# RH031_1.net
KiCad netlist of a schematic drawn in EAGLE
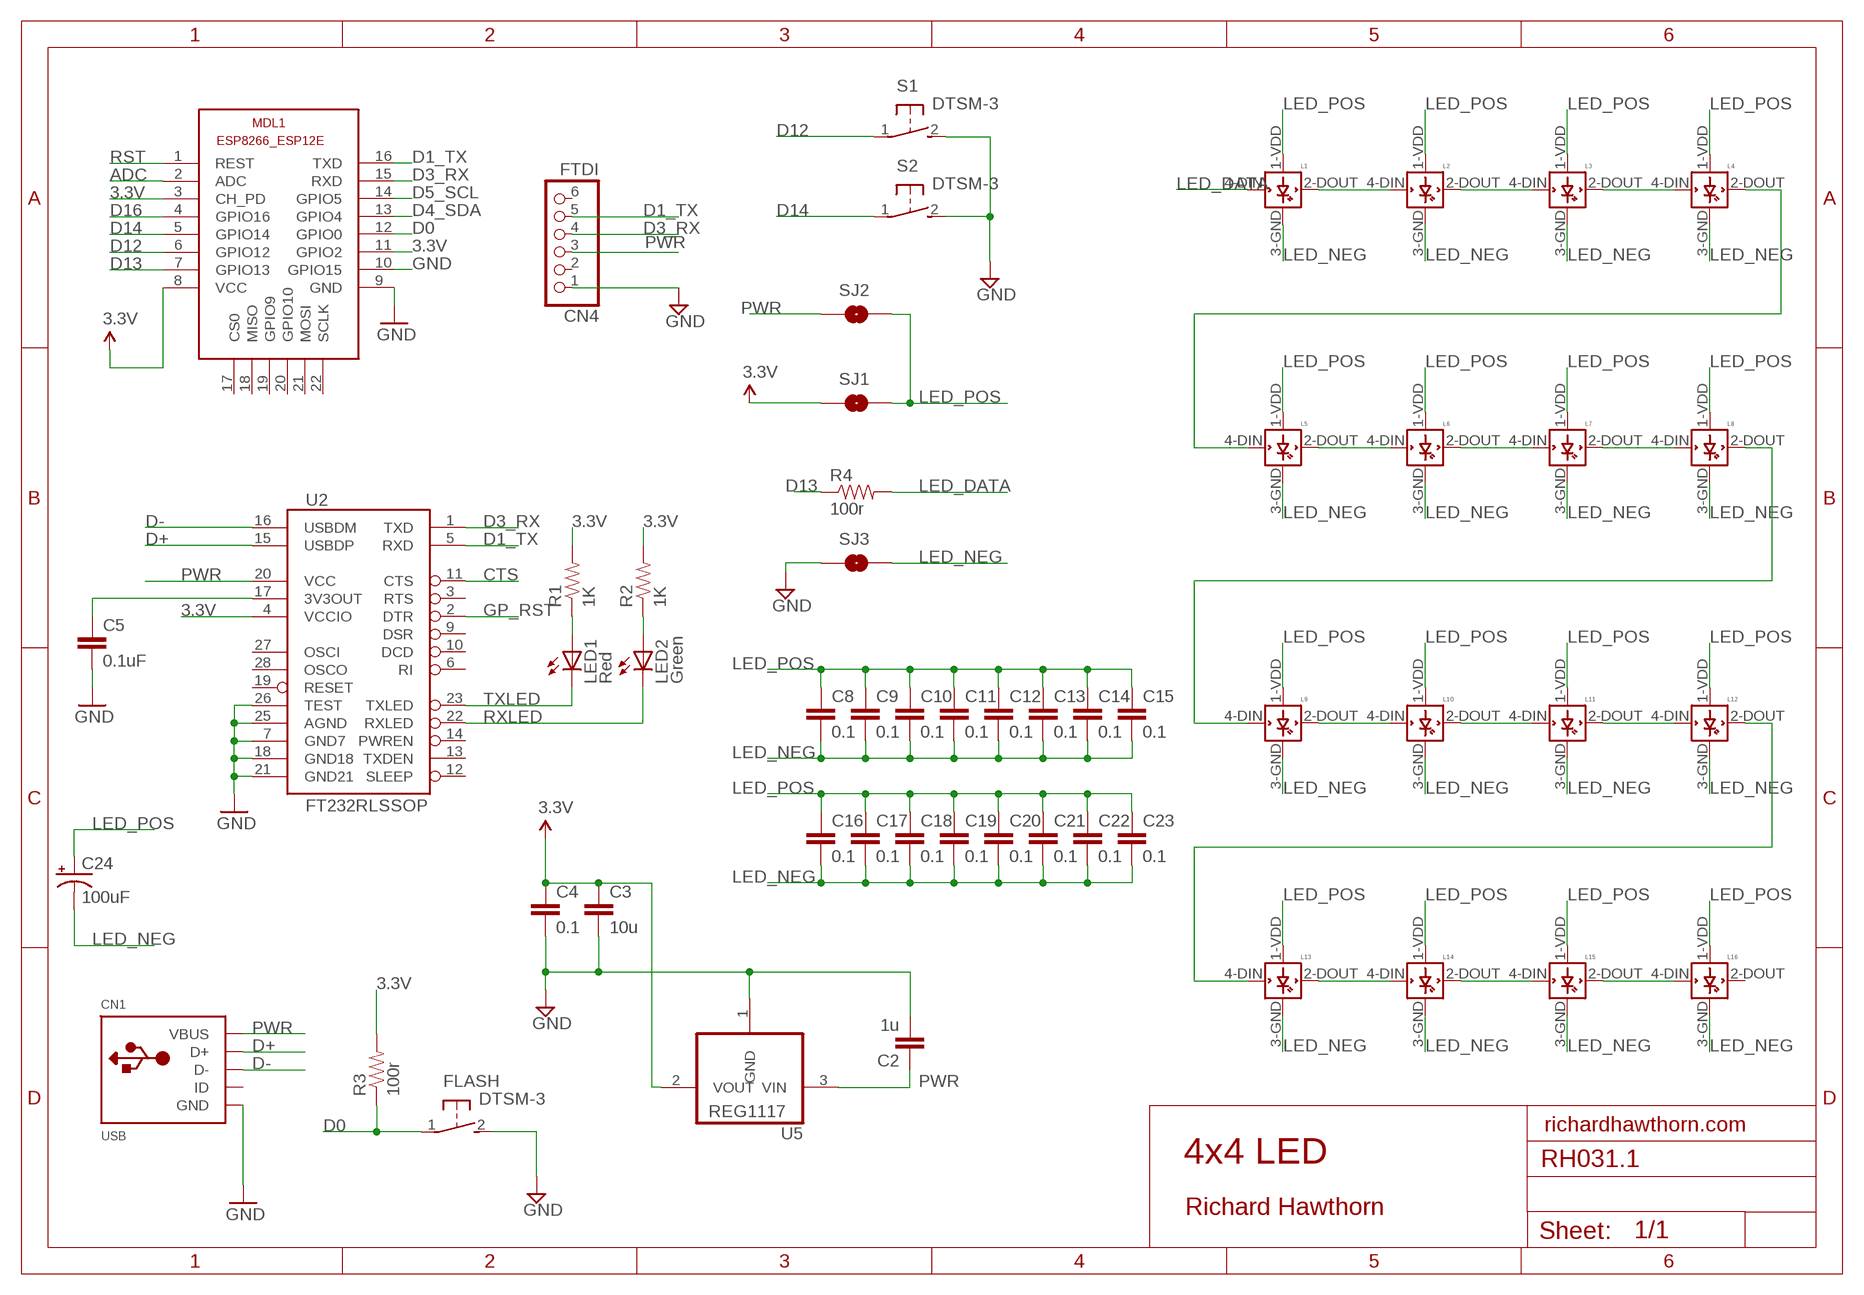
[diagram p0: schematic, sheet 1]

(export (version "E")
  (design (tool "Eeschema 10.0.6"))
  (components
    (comp (ref "C2")
      (value "1u")
      (footprint "eagle-import:0603-CAP")
      (libsource (lib "eagle-import") (part "CAP0603-CAP"))
    )
    (comp (ref "C3")
      (value "10u")
      (footprint "eagle-import:0805-CAP")
      (libsource (lib "eagle-import") (part "CAP0805-CAP"))
    )
    (comp (ref "C4")
      (value "0.1")
      (footprint "eagle-import:0603-CAP")
      (libsource (lib "eagle-import") (part "CAP0603-CAP"))
    )
    (comp (ref "C5")
      (value "0.1uF")
      (footprint "eagle-import:0805")
      (libsource (lib "eagle-import") (part "SparkFun_CAP0805"))
    )
    (comp (ref "C8")
      (value "0.1")
      (footprint "eagle-import:0603-CAP")
      (libsource (lib "eagle-import") (part "CAP0603-CAP"))
    )
    (comp (ref "C9")
      (value "0.1")
      (footprint "eagle-import:0603-CAP")
      (libsource (lib "eagle-import") (part "CAP0603-CAP"))
    )
    (comp (ref "C10")
      (value "0.1")
      (footprint "eagle-import:0603-CAP")
      (libsource (lib "eagle-import") (part "CAP0603-CAP"))
    )
    (comp (ref "C11")
      (value "0.1")
      (footprint "eagle-import:0603-CAP")
      (libsource (lib "eagle-import") (part "CAP0603-CAP"))
    )
    (comp (ref "C12")
      (value "0.1")
      (footprint "eagle-import:0603-CAP")
      (libsource (lib "eagle-import") (part "CAP0603-CAP"))
    )
    (comp (ref "C13")
      (value "0.1")
      (footprint "eagle-import:0603-CAP")
      (libsource (lib "eagle-import") (part "CAP0603-CAP"))
    )
    (comp (ref "C14")
      (value "0.1")
      (footprint "eagle-import:0603-CAP")
      (libsource (lib "eagle-import") (part "CAP0603-CAP"))
    )
    (comp (ref "C15")
      (value "0.1")
      (footprint "eagle-import:0603-CAP")
      (libsource (lib "eagle-import") (part "CAP0603-CAP"))
    )
    (comp (ref "C16")
      (value "0.1")
      (footprint "eagle-import:0603-CAP")
      (libsource (lib "eagle-import") (part "CAP0603-CAP"))
    )
    (comp (ref "C17")
      (value "0.1")
      (footprint "eagle-import:0603-CAP")
      (libsource (lib "eagle-import") (part "CAP0603-CAP"))
    )
    (comp (ref "C18")
      (value "0.1")
      (footprint "eagle-import:0603-CAP")
      (libsource (lib "eagle-import") (part "CAP0603-CAP"))
    )
    (comp (ref "C19")
      (value "0.1")
      (footprint "eagle-import:0603-CAP")
      (libsource (lib "eagle-import") (part "CAP0603-CAP"))
    )
    (comp (ref "C20")
      (value "0.1")
      (footprint "eagle-import:0603-CAP")
      (libsource (lib "eagle-import") (part "CAP0603-CAP"))
    )
    (comp (ref "C21")
      (value "0.1")
      (footprint "eagle-import:0603-CAP")
      (libsource (lib "eagle-import") (part "CAP0603-CAP"))
    )
    (comp (ref "C22")
      (value "0.1")
      (footprint "eagle-import:0603-CAP")
      (libsource (lib "eagle-import") (part "CAP0603-CAP"))
    )
    (comp (ref "C23")
      (value "0.1")
      (footprint "eagle-import:0603-CAP")
      (libsource (lib "eagle-import") (part "CAP0603-CAP"))
    )
    (comp (ref "C24")
      (value "100uF")
      (footprint "eagle-import:EIA7343")
      (libsource (lib "eagle-import") (part "100UF-10V-10%(TANT)"))
    )
    (comp (ref "CN1")
      (value "USB")
      (footprint "eagle-import:USB-MINIB")
      (libsource (lib "eagle-import") (part "USBMINIB"))
    )
    (comp (ref "CN4")
      (value "FTDI")
      (footprint "eagle-import:1X06")
      (libsource (lib "eagle-import") (part "PINHD-1X6"))
    )
    (comp (ref "FLASH")
      (value "DTSM-3")
      (footprint "eagle-import:DTSM-3")
      (libsource (lib "eagle-import") (part "DTSM-3"))
    )
    (comp (ref "L1")
      (value "WS2812B")
      (footprint "eagle-import:WS2812B")
      (libsource (lib "eagle-import") (part "WS2812B"))
    )
    (comp (ref "L2")
      (value "WS2812B")
      (footprint "eagle-import:WS2812B")
      (libsource (lib "eagle-import") (part "WS2812B"))
    )
    (comp (ref "L3")
      (value "WS2812B")
      (footprint "eagle-import:WS2812B")
      (libsource (lib "eagle-import") (part "WS2812B"))
    )
    (comp (ref "L4")
      (value "WS2812B")
      (footprint "eagle-import:WS2812B")
      (libsource (lib "eagle-import") (part "WS2812B"))
    )
    (comp (ref "L5")
      (value "WS2812B")
      (footprint "eagle-import:WS2812B")
      (libsource (lib "eagle-import") (part "WS2812B"))
    )
    (comp (ref "L6")
      (value "WS2812B")
      (footprint "eagle-import:WS2812B")
      (libsource (lib "eagle-import") (part "WS2812B"))
    )
    (comp (ref "L7")
      (value "WS2812B")
      (footprint "eagle-import:WS2812B")
      (libsource (lib "eagle-import") (part "WS2812B"))
    )
    (comp (ref "L8")
      (value "WS2812B")
      (footprint "eagle-import:WS2812B")
      (libsource (lib "eagle-import") (part "WS2812B"))
    )
    (comp (ref "L9")
      (value "WS2812B")
      (footprint "eagle-import:WS2812B")
      (libsource (lib "eagle-import") (part "WS2812B"))
    )
    (comp (ref "L10")
      (value "WS2812B")
      (footprint "eagle-import:WS2812B")
      (libsource (lib "eagle-import") (part "WS2812B"))
    )
    (comp (ref "L11")
      (value "WS2812B")
      (footprint "eagle-import:WS2812B")
      (libsource (lib "eagle-import") (part "WS2812B"))
    )
    (comp (ref "L12")
      (value "WS2812B")
      (footprint "eagle-import:WS2812B")
      (libsource (lib "eagle-import") (part "WS2812B"))
    )
    (comp (ref "L13")
      (value "WS2812B")
      (footprint "eagle-import:WS2812B")
      (libsource (lib "eagle-import") (part "WS2812B"))
    )
    (comp (ref "L14")
      (value "WS2812B")
      (footprint "eagle-import:WS2812B")
      (libsource (lib "eagle-import") (part "WS2812B"))
    )
    (comp (ref "L15")
      (value "WS2812B")
      (footprint "eagle-import:WS2812B")
      (libsource (lib "eagle-import") (part "WS2812B"))
    )
    (comp (ref "L16")
      (value "WS2812B")
      (footprint "eagle-import:WS2812B")
      (libsource (lib "eagle-import") (part "WS2812B"))
    )
    (comp (ref "LED1")
      (value "Red")
      (footprint "eagle-import:CHIPLED_0805")
      (libsource (lib "eagle-import") (part "LEDCHIPLED_0805"))
    )
    (comp (ref "LED2")
      (value "Green")
      (footprint "eagle-import:CHIPLED_0805")
      (libsource (lib "eagle-import") (part "LEDCHIPLED_0805"))
    )
    (comp (ref "MDL1")
      (value "ESP8266-12EESP8266-ESP12E")
      (footprint "eagle-import:ESP8266-ESP12E")
      (libsource (lib "eagle-import") (part "ESP8266-12EESP8266-ESP12E"))
    )
    (comp (ref "R1")
      (value "1K")
      (footprint "eagle-import:0805")
      (libsource (lib "eagle-import") (part "SparkFun_RESISTOR0805-RES"))
    )
    (comp (ref "R2")
      (value "1K")
      (footprint "eagle-import:0805")
      (libsource (lib "eagle-import") (part "SparkFun_RESISTOR0805-RES"))
    )
    (comp (ref "R3")
      (value "100r")
      (footprint "eagle-import:0603-RES")
      (libsource (lib "eagle-import") (part "RESISTOR0603-RES"))
    )
    (comp (ref "R4")
      (value "100r")
      (footprint "eagle-import:0603-RES")
      (libsource (lib "eagle-import") (part "RESISTOR0603-RES"))
    )
    (comp (ref "S1")
      (value "DTSM-3")
      (footprint "eagle-import:DTSM-3")
      (libsource (lib "eagle-import") (part "DTSM-3"))
    )
    (comp (ref "S2")
      (value "DTSM-3")
      (footprint "eagle-import:DTSM-3")
      (libsource (lib "eagle-import") (part "DTSM-3"))
    )
    (comp (ref "SJ1")
      (value "SOLDERJUMPERNO")
      (footprint "eagle-import:SJ_2S-NO")
      (libsource (lib "eagle-import") (part "SOLDERJUMPERNO"))
    )
    (comp (ref "SJ2")
      (value "SOLDERJUMPERNO")
      (footprint "eagle-import:SJ_2S-NO")
      (libsource (lib "eagle-import") (part "SOLDERJUMPERNO"))
    )
    (comp (ref "SJ3")
      (value "SOLDERJUMPERNO")
      (footprint "eagle-import:SJ_2S-NO")
      (libsource (lib "eagle-import") (part "SOLDERJUMPERNO"))
    )
    (comp (ref "U2")
      (value "FT232RLSSOP")
      (footprint "eagle-import:SSOP28DB")
      (libsource (lib "eagle-import") (part "FT232RLSSOP"))
    )
    (comp (ref "U5")
      (value "REG1117")
      (footprint "eagle-import:SOT223")
      (libsource (lib "eagle-import") (part "REG1117"))
    )
  )
  (nets
    (net (code "1") (name "/ADC") (class "Default")
      (node (ref "MDL1") (pin "2") (pinfunction "ADC_2") (pintype "bidirectional"))
    )
    (net (code "2") (name "/CTS") (class "Default")
      (node (ref "U2") (pin "11") (pinfunction "CTS_11") (pintype "input"))
    )
    (net (code "3") (name "/D+") (class "Default")
      (node (ref "CN1") (pin "D+") (pinfunction "D+_D+") (pintype "bidirectional"))
      (node (ref "U2") (pin "15") (pinfunction "USBDP_15") (pintype "bidirectional"))
    )
    (net (code "4") (name "/D-") (class "Default")
      (node (ref "CN1") (pin "D-") (pinfunction "D-_D-") (pintype "bidirectional"))
      (node (ref "U2") (pin "16") (pinfunction "USBDM_16") (pintype "bidirectional"))
    )
    (net (code "5") (name "/D0") (class "Default")
      (node (ref "FLASH") (pin "1") (pinfunction "1_1") (pintype "passive"))
      (node (ref "MDL1") (pin "12") (pinfunction "GPIO0_12") (pintype "bidirectional"))
      (node (ref "R3") (pin "1") (pinfunction "1_1") (pintype "passive"))
    )
    (net (code "6") (name "/D1_TX") (class "Default")
      (node (ref "CN4") (pin "5") (pinfunction "5_5") (pintype "passive"))
      (node (ref "MDL1") (pin "16") (pinfunction "TXD_16") (pintype "bidirectional"))
      (node (ref "U2") (pin "5") (pinfunction "RXD_5") (pintype "input"))
    )
    (net (code "7") (name "/D3_RX") (class "Default")
      (node (ref "CN4") (pin "4") (pinfunction "4_4") (pintype "passive"))
      (node (ref "MDL1") (pin "15") (pinfunction "RXD_15") (pintype "bidirectional"))
      (node (ref "U2") (pin "1") (pinfunction "TXD_1") (pintype "output"))
    )
    (net (code "8") (name "/D4_SDA") (class "Default")
      (node (ref "MDL1") (pin "13") (pinfunction "GPIO4_13") (pintype "bidirectional"))
    )
    (net (code "9") (name "/D5_SCL") (class "Default")
      (node (ref "MDL1") (pin "14") (pinfunction "GPIO5_14") (pintype "bidirectional"))
    )
    (net (code "10") (name "/D12") (class "Default")
      (node (ref "MDL1") (pin "6") (pinfunction "GPIO12_6") (pintype "bidirectional"))
      (node (ref "S1") (pin "1") (pinfunction "1_1") (pintype "passive"))
    )
    (net (code "11") (name "/D13") (class "Default")
      (node (ref "MDL1") (pin "7") (pinfunction "GPIO13_7") (pintype "bidirectional"))
      (node (ref "R4") (pin "1") (pinfunction "1_1") (pintype "passive"))
    )
    (net (code "12") (name "/D14") (class "Default")
      (node (ref "MDL1") (pin "5") (pinfunction "GPIO14_5") (pintype "bidirectional"))
      (node (ref "S2") (pin "1") (pinfunction "1_1") (pintype "passive"))
    )
    (net (code "13") (name "/D16") (class "Default")
      (node (ref "MDL1") (pin "4") (pinfunction "GPIO16_4") (pintype "bidirectional"))
    )
    (net (code "14") (name "/GP_RST") (class "Default")
      (node (ref "U2") (pin "2") (pinfunction "DTR_2") (pintype "output"))
    )
    (net (code "15") (name "/LED_DATA") (class "Default")
      (node (ref "L1") (pin "4-DIN") (pinfunction "DIN_4-DIN") (pintype "input"))
      (node (ref "R4") (pin "2") (pinfunction "2_2") (pintype "passive"))
    )
    (net (code "16") (name "/LED_NEG") (class "Default")
      (node (ref "C10") (pin "2") (pinfunction "2_2") (pintype "passive"))
      (node (ref "C11") (pin "2") (pinfunction "2_2") (pintype "passive"))
      (node (ref "C12") (pin "2") (pinfunction "2_2") (pintype "passive"))
      (node (ref "C13") (pin "2") (pinfunction "2_2") (pintype "passive"))
      (node (ref "C14") (pin "2") (pinfunction "2_2") (pintype "passive"))
      (node (ref "C15") (pin "2") (pinfunction "2_2") (pintype "passive"))
      (node (ref "C16") (pin "2") (pinfunction "2_2") (pintype "passive"))
      (node (ref "C17") (pin "2") (pinfunction "2_2") (pintype "passive"))
      (node (ref "C18") (pin "2") (pinfunction "2_2") (pintype "passive"))
      (node (ref "C19") (pin "2") (pinfunction "2_2") (pintype "passive"))
      (node (ref "C20") (pin "2") (pinfunction "2_2") (pintype "passive"))
      (node (ref "C21") (pin "2") (pinfunction "2_2") (pintype "passive"))
      (node (ref "C22") (pin "2") (pinfunction "2_2") (pintype "passive"))
      (node (ref "C23") (pin "2") (pinfunction "2_2") (pintype "passive"))
      (node (ref "C24") (pin "C") (pinfunction "-_C") (pintype "passive"))
      (node (ref "C8") (pin "2") (pinfunction "2_2") (pintype "passive"))
      (node (ref "C9") (pin "2") (pinfunction "2_2") (pintype "passive"))
      (node (ref "L1") (pin "3-GND") (pinfunction "GND_3-GND") (pintype "bidirectional"))
      (node (ref "L10") (pin "3-GND") (pinfunction "GND_3-GND") (pintype "bidirectional"))
      (node (ref "L11") (pin "3-GND") (pinfunction "GND_3-GND") (pintype "bidirectional"))
      (node (ref "L12") (pin "3-GND") (pinfunction "GND_3-GND") (pintype "bidirectional"))
      (node (ref "L13") (pin "3-GND") (pinfunction "GND_3-GND") (pintype "bidirectional"))
      (node (ref "L14") (pin "3-GND") (pinfunction "GND_3-GND") (pintype "bidirectional"))
      (node (ref "L15") (pin "3-GND") (pinfunction "GND_3-GND") (pintype "bidirectional"))
      (node (ref "L16") (pin "3-GND") (pinfunction "GND_3-GND") (pintype "bidirectional"))
      (node (ref "L2") (pin "3-GND") (pinfunction "GND_3-GND") (pintype "bidirectional"))
      (node (ref "L3") (pin "3-GND") (pinfunction "GND_3-GND") (pintype "bidirectional"))
      (node (ref "L4") (pin "3-GND") (pinfunction "GND_3-GND") (pintype "bidirectional"))
      (node (ref "L5") (pin "3-GND") (pinfunction "GND_3-GND") (pintype "bidirectional"))
      (node (ref "L6") (pin "3-GND") (pinfunction "GND_3-GND") (pintype "bidirectional"))
      (node (ref "L7") (pin "3-GND") (pinfunction "GND_3-GND") (pintype "bidirectional"))
      (node (ref "L8") (pin "3-GND") (pinfunction "GND_3-GND") (pintype "bidirectional"))
      (node (ref "L9") (pin "3-GND") (pinfunction "GND_3-GND") (pintype "bidirectional"))
      (node (ref "SJ3") (pin "2") (pinfunction "2_2") (pintype "passive"))
    )
    (net (code "17") (name "/LED_POS") (class "Default")
      (node (ref "C10") (pin "1") (pinfunction "1_1") (pintype "passive"))
      (node (ref "C11") (pin "1") (pinfunction "1_1") (pintype "passive"))
      (node (ref "C12") (pin "1") (pinfunction "1_1") (pintype "passive"))
      (node (ref "C13") (pin "1") (pinfunction "1_1") (pintype "passive"))
      (node (ref "C14") (pin "1") (pinfunction "1_1") (pintype "passive"))
      (node (ref "C15") (pin "1") (pinfunction "1_1") (pintype "passive"))
      (node (ref "C16") (pin "1") (pinfunction "1_1") (pintype "passive"))
      (node (ref "C17") (pin "1") (pinfunction "1_1") (pintype "passive"))
      (node (ref "C18") (pin "1") (pinfunction "1_1") (pintype "passive"))
      (node (ref "C19") (pin "1") (pinfunction "1_1") (pintype "passive"))
      (node (ref "C20") (pin "1") (pinfunction "1_1") (pintype "passive"))
      (node (ref "C21") (pin "1") (pinfunction "1_1") (pintype "passive"))
      (node (ref "C22") (pin "1") (pinfunction "1_1") (pintype "passive"))
      (node (ref "C23") (pin "1") (pinfunction "1_1") (pintype "passive"))
      (node (ref "C24") (pin "A") (pinfunction "+_A") (pintype "passive"))
      (node (ref "C8") (pin "1") (pinfunction "1_1") (pintype "passive"))
      (node (ref "C9") (pin "1") (pinfunction "1_1") (pintype "passive"))
      (node (ref "L1") (pin "1-VDD") (pinfunction "VDD_1-VDD") (pintype "bidirectional"))
      (node (ref "L10") (pin "1-VDD") (pinfunction "VDD_1-VDD") (pintype "bidirectional"))
      (node (ref "L11") (pin "1-VDD") (pinfunction "VDD_1-VDD") (pintype "bidirectional"))
      (node (ref "L12") (pin "1-VDD") (pinfunction "VDD_1-VDD") (pintype "bidirectional"))
      (node (ref "L13") (pin "1-VDD") (pinfunction "VDD_1-VDD") (pintype "bidirectional"))
      (node (ref "L14") (pin "1-VDD") (pinfunction "VDD_1-VDD") (pintype "bidirectional"))
      (node (ref "L15") (pin "1-VDD") (pinfunction "VDD_1-VDD") (pintype "bidirectional"))
      (node (ref "L16") (pin "1-VDD") (pinfunction "VDD_1-VDD") (pintype "bidirectional"))
      (node (ref "L2") (pin "1-VDD") (pinfunction "VDD_1-VDD") (pintype "bidirectional"))
      (node (ref "L3") (pin "1-VDD") (pinfunction "VDD_1-VDD") (pintype "bidirectional"))
      (node (ref "L4") (pin "1-VDD") (pinfunction "VDD_1-VDD") (pintype "bidirectional"))
      (node (ref "L5") (pin "1-VDD") (pinfunction "VDD_1-VDD") (pintype "bidirectional"))
      (node (ref "L6") (pin "1-VDD") (pinfunction "VDD_1-VDD") (pintype "bidirectional"))
      (node (ref "L7") (pin "1-VDD") (pinfunction "VDD_1-VDD") (pintype "bidirectional"))
      (node (ref "L8") (pin "1-VDD") (pinfunction "VDD_1-VDD") (pintype "bidirectional"))
      (node (ref "L9") (pin "1-VDD") (pinfunction "VDD_1-VDD") (pintype "bidirectional"))
      (node (ref "SJ1") (pin "2") (pinfunction "2_2") (pintype "passive"))
      (node (ref "SJ2") (pin "2") (pinfunction "2_2") (pintype "passive"))
    )
    (net (code "18") (name "/PWR") (class "Default")
      (node (ref "C2") (pin "1") (pinfunction "1_1") (pintype "passive"))
      (node (ref "CN1") (pin "VBUS") (pinfunction "VBUS_VBUS") (pintype "power_in"))
      (node (ref "CN4") (pin "3") (pinfunction "3_3") (pintype "passive"))
      (node (ref "SJ2") (pin "1") (pinfunction "1_1") (pintype "passive"))
      (node (ref "U2") (pin "20") (pinfunction "VCC_20") (pintype "power_in"))
      (node (ref "U5") (pin "3") (pinfunction "VIN_3") (pintype "input"))
    )
    (net (code "19") (name "/RST") (class "Default")
      (node (ref "MDL1") (pin "1") (pinfunction "REST_1") (pintype "bidirectional"))
    )
    (net (code "20") (name "/RXLED") (class "Default")
      (node (ref "LED2") (pin "C") (pinfunction "C_C") (pintype "passive"))
      (node (ref "U2") (pin "22") (pinfunction "RXLED_22") (pintype "input"))
    )
    (net (code "21") (name "/TXLED") (class "Default")
      (node (ref "LED1") (pin "C") (pinfunction "C_C") (pintype "passive"))
      (node (ref "U2") (pin "23") (pinfunction "TXLED_23") (pintype "input"))
    )
    (net (code "22") (name "3.3V") (class "Default")
      (node (ref "C3") (pin "1") (pinfunction "1_1") (pintype "passive"))
      (node (ref "C4") (pin "1") (pinfunction "1_1") (pintype "passive"))
      (node (ref "MDL1") (pin "11") (pinfunction "GPIO2_11") (pintype "bidirectional"))
      (node (ref "MDL1") (pin "3") (pinfunction "CH_PD_3") (pintype "bidirectional"))
      (node (ref "MDL1") (pin "8") (pinfunction "VCC_8") (pintype "bidirectional"))
      (node (ref "R1") (pin "2") (pinfunction "2_2") (pintype "passive"))
      (node (ref "R2") (pin "2") (pinfunction "2_2") (pintype "passive"))
      (node (ref "R3") (pin "2") (pinfunction "2_2") (pintype "passive"))
      (node (ref "SJ1") (pin "1") (pinfunction "1_1") (pintype "passive"))
      (node (ref "U2") (pin "4") (pinfunction "VCCIO_4") (pintype "power_in"))
      (node (ref "U5") (pin "2") (pinfunction "VOUT_2") (pintype "output"))
    )
    (net (code "23") (name "GND") (class "Default")
      (node (ref "C2") (pin "2") (pinfunction "2_2") (pintype "passive"))
      (node (ref "C3") (pin "2") (pinfunction "2_2") (pintype "passive"))
      (node (ref "C4") (pin "2") (pinfunction "2_2") (pintype "passive"))
      (node (ref "C5") (pin "2") (pinfunction "2_2") (pintype "passive"))
      (node (ref "CN1") (pin "GND") (pinfunction "GND_GND") (pintype "power_in"))
      (node (ref "CN4") (pin "1") (pinfunction "1_1") (pintype "passive"))
      (node (ref "FLASH") (pin "2") (pinfunction "2_2") (pintype "passive"))
      (node (ref "MDL1") (pin "10") (pinfunction "GPIO15_10") (pintype "bidirectional"))
      (node (ref "MDL1") (pin "9") (pinfunction "GND_9") (pintype "bidirectional"))
      (node (ref "S1") (pin "2") (pinfunction "2_2") (pintype "passive"))
      (node (ref "S2") (pin "2") (pinfunction "2_2") (pintype "passive"))
      (node (ref "SJ3") (pin "1") (pinfunction "1_1") (pintype "passive"))
      (node (ref "U2") (pin "18") (pinfunction "GND18_18") (pintype "power_in"))
      (node (ref "U2") (pin "21") (pinfunction "GND21_21") (pintype "power_in"))
      (node (ref "U2") (pin "25") (pinfunction "AGND_25") (pintype "power_in"))
      (node (ref "U2") (pin "26") (pinfunction "TEST_26") (pintype "input"))
      (node (ref "U2") (pin "7") (pinfunction "GND7_7") (pintype "power_in"))
      (node (ref "U5") (pin "1") (pinfunction "GND_1") (pintype "power_in"))
    )
    (net (code "24") (name "Net-(L1-DOUT)") (class "Default")
      (node (ref "L1") (pin "2-DOUT") (pinfunction "DOUT_2-DOUT") (pintype "output"))
      (node (ref "L2") (pin "4-DIN") (pinfunction "DIN_4-DIN") (pintype "input"))
    )
    (net (code "25") (name "Net-(L2-DOUT)") (class "Default")
      (node (ref "L2") (pin "2-DOUT") (pinfunction "DOUT_2-DOUT") (pintype "output"))
      (node (ref "L3") (pin "4-DIN") (pinfunction "DIN_4-DIN") (pintype "input"))
    )
    (net (code "26") (name "Net-(L3-DOUT)") (class "Default")
      (node (ref "L3") (pin "2-DOUT") (pinfunction "DOUT_2-DOUT") (pintype "output"))
      (node (ref "L4") (pin "4-DIN") (pinfunction "DIN_4-DIN") (pintype "input"))
    )
    (net (code "27") (name "Net-(L4-DOUT)") (class "Default")
      (node (ref "L4") (pin "2-DOUT") (pinfunction "DOUT_2-DOUT") (pintype "output"))
      (node (ref "L5") (pin "4-DIN") (pinfunction "DIN_4-DIN") (pintype "input"))
    )
    (net (code "28") (name "Net-(L5-DOUT)") (class "Default")
      (node (ref "L5") (pin "2-DOUT") (pinfunction "DOUT_2-DOUT") (pintype "output"))
      (node (ref "L6") (pin "4-DIN") (pinfunction "DIN_4-DIN") (pintype "input"))
    )
    (net (code "29") (name "Net-(L6-DOUT)") (class "Default")
      (node (ref "L6") (pin "2-DOUT") (pinfunction "DOUT_2-DOUT") (pintype "output"))
      (node (ref "L7") (pin "4-DIN") (pinfunction "DIN_4-DIN") (pintype "input"))
    )
    (net (code "30") (name "Net-(L7-DOUT)") (class "Default")
      (node (ref "L7") (pin "2-DOUT") (pinfunction "DOUT_2-DOUT") (pintype "output"))
      (node (ref "L8") (pin "4-DIN") (pinfunction "DIN_4-DIN") (pintype "input"))
    )
    (net (code "31") (name "Net-(L8-DOUT)") (class "Default")
      (node (ref "L8") (pin "2-DOUT") (pinfunction "DOUT_2-DOUT") (pintype "output"))
      (node (ref "L9") (pin "4-DIN") (pinfunction "DIN_4-DIN") (pintype "input"))
    )
    (net (code "32") (name "Net-(L10-DIN)") (class "Default")
      (node (ref "L10") (pin "4-DIN") (pinfunction "DIN_4-DIN") (pintype "input"))
      (node (ref "L9") (pin "2-DOUT") (pinfunction "DOUT_2-DOUT") (pintype "output"))
    )
    (net (code "33") (name "Net-(L10-DOUT)") (class "Default")
      (node (ref "L10") (pin "2-DOUT") (pinfunction "DOUT_2-DOUT") (pintype "output"))
      (node (ref "L11") (pin "4-DIN") (pinfunction "DIN_4-DIN") (pintype "input"))
    )
    (net (code "34") (name "Net-(L11-DOUT)") (class "Default")
      (node (ref "L11") (pin "2-DOUT") (pinfunction "DOUT_2-DOUT") (pintype "output"))
      (node (ref "L12") (pin "4-DIN") (pinfunction "DIN_4-DIN") (pintype "input"))
    )
    (net (code "35") (name "Net-(L12-DOUT)") (class "Default")
      (node (ref "L12") (pin "2-DOUT") (pinfunction "DOUT_2-DOUT") (pintype "output"))
      (node (ref "L13") (pin "4-DIN") (pinfunction "DIN_4-DIN") (pintype "input"))
    )
    (net (code "36") (name "Net-(L13-DOUT)") (class "Default")
      (node (ref "L13") (pin "2-DOUT") (pinfunction "DOUT_2-DOUT") (pintype "output"))
      (node (ref "L14") (pin "4-DIN") (pinfunction "DIN_4-DIN") (pintype "input"))
    )
    (net (code "37") (name "Net-(L14-DOUT)") (class "Default")
      (node (ref "L14") (pin "2-DOUT") (pinfunction "DOUT_2-DOUT") (pintype "output"))
      (node (ref "L15") (pin "4-DIN") (pinfunction "DIN_4-DIN") (pintype "input"))
    )
    (net (code "38") (name "Net-(L15-DOUT)") (class "Default")
      (node (ref "L15") (pin "2-DOUT") (pinfunction "DOUT_2-DOUT") (pintype "output"))
      (node (ref "L16") (pin "4-DIN") (pinfunction "DIN_4-DIN") (pintype "input"))
    )
    (net (code "39") (name "Net-(LED1-PadA)") (class "Default")
      (node (ref "LED1") (pin "A") (pinfunction "A_A") (pintype "passive"))
      (node (ref "R1") (pin "1") (pinfunction "1_1") (pintype "passive"))
    )
    (net (code "40") (name "Net-(LED2-PadA)") (class "Default")
      (node (ref "LED2") (pin "A") (pinfunction "A_A") (pintype "passive"))
      (node (ref "R2") (pin "1") (pinfunction "1_1") (pintype "passive"))
    )
    (net (code "41") (name "Net-(U2-3V3OUT)") (class "Default")
      (node (ref "C5") (pin "1") (pinfunction "1_1") (pintype "passive"))
      (node (ref "U2") (pin "17") (pinfunction "3V3OUT_17") (pintype "output"))
    )
    (net (code "42") (name "unconnected-(CN1-PadID)") (class "Default")
      (node (ref "CN1") (pin "ID") (pinfunction "ID_ID") (pintype "bidirectional"))
    )
    (net (code "43") (name "unconnected-(CN4-Pad2)") (class "Default")
      (node (ref "CN4") (pin "2") (pinfunction "2_2") (pintype "passive"))
    )
    (net (code "44") (name "unconnected-(CN4-Pad6)") (class "Default")
      (node (ref "CN4") (pin "6") (pinfunction "6_6") (pintype "passive"))
    )
    (net (code "45") (name "unconnected-(L16-DOUT-Pad2-DOUT)") (class "Default")
      (node (ref "L16") (pin "2-DOUT") (pinfunction "DOUT_2-DOUT") (pintype "output"))
    )
    (net (code "46") (name "unconnected-(MDL1-CS0-Pad17)") (class "Default")
      (node (ref "MDL1") (pin "17") (pinfunction "CS0_17") (pintype "bidirectional"))
    )
    (net (code "47") (name "unconnected-(MDL1-GPIO9-Pad19)") (class "Default")
      (node (ref "MDL1") (pin "19") (pinfunction "GPIO9_19") (pintype "bidirectional"))
    )
    (net (code "48") (name "unconnected-(MDL1-GPIO10-Pad20)") (class "Default")
      (node (ref "MDL1") (pin "20") (pinfunction "GPIO10_20") (pintype "bidirectional"))
    )
    (net (code "49") (name "unconnected-(MDL1-MISO-Pad18)") (class "Default")
      (node (ref "MDL1") (pin "18") (pinfunction "MISO_18") (pintype "bidirectional"))
    )
    (net (code "50") (name "unconnected-(MDL1-MOSI-Pad21)") (class "Default")
      (node (ref "MDL1") (pin "21") (pinfunction "MOSI_21") (pintype "bidirectional"))
    )
    (net (code "51") (name "unconnected-(MDL1-SCLK-Pad22)") (class "Default")
      (node (ref "MDL1") (pin "22") (pinfunction "SCLK_22") (pintype "bidirectional"))
    )
    (net (code "52") (name "unconnected-(U2-DCD-Pad10)") (class "Default")
      (node (ref "U2") (pin "10") (pinfunction "DCD_10") (pintype "input"))
    )
    (net (code "53") (name "unconnected-(U2-DSR-Pad9)") (class "Default")
      (node (ref "U2") (pin "9") (pinfunction "DSR_9") (pintype "input"))
    )
    (net (code "54") (name "unconnected-(U2-OSCI-Pad27)") (class "Default")
      (node (ref "U2") (pin "27") (pinfunction "OSCI_27") (pintype "input"))
    )
    (net (code "55") (name "unconnected-(U2-OSCO-Pad28)") (class "Default")
      (node (ref "U2") (pin "28") (pinfunction "OSCO_28") (pintype "output"))
    )
    (net (code "56") (name "unconnected-(U2-PWREN-Pad14)") (class "Default")
      (node (ref "U2") (pin "14") (pinfunction "PWREN_14") (pintype "input"))
    )
    (net (code "57") (name "unconnected-(U2-RESET-Pad19)") (class "Default")
      (node (ref "U2") (pin "19") (pinfunction "RESET_19") (pintype "input"))
    )
    (net (code "58") (name "unconnected-(U2-RI-Pad6)") (class "Default")
      (node (ref "U2") (pin "6") (pinfunction "RI_6") (pintype "input"))
    )
    (net (code "59") (name "unconnected-(U2-RTS-Pad3)") (class "Default")
      (node (ref "U2") (pin "3") (pinfunction "RTS_3") (pintype "output"))
    )
    (net (code "60") (name "unconnected-(U2-SLEEP-Pad12)") (class "Default")
      (node (ref "U2") (pin "12") (pinfunction "SLEEP_12") (pintype "input"))
    )
    (net (code "61") (name "unconnected-(U2-TXDEN-Pad13)") (class "Default")
      (node (ref "U2") (pin "13") (pinfunction "TXDEN_13") (pintype "input"))
    )
  )
)
